# thermometer.net
KiCad netlist of a schematic drawn in EAGLE
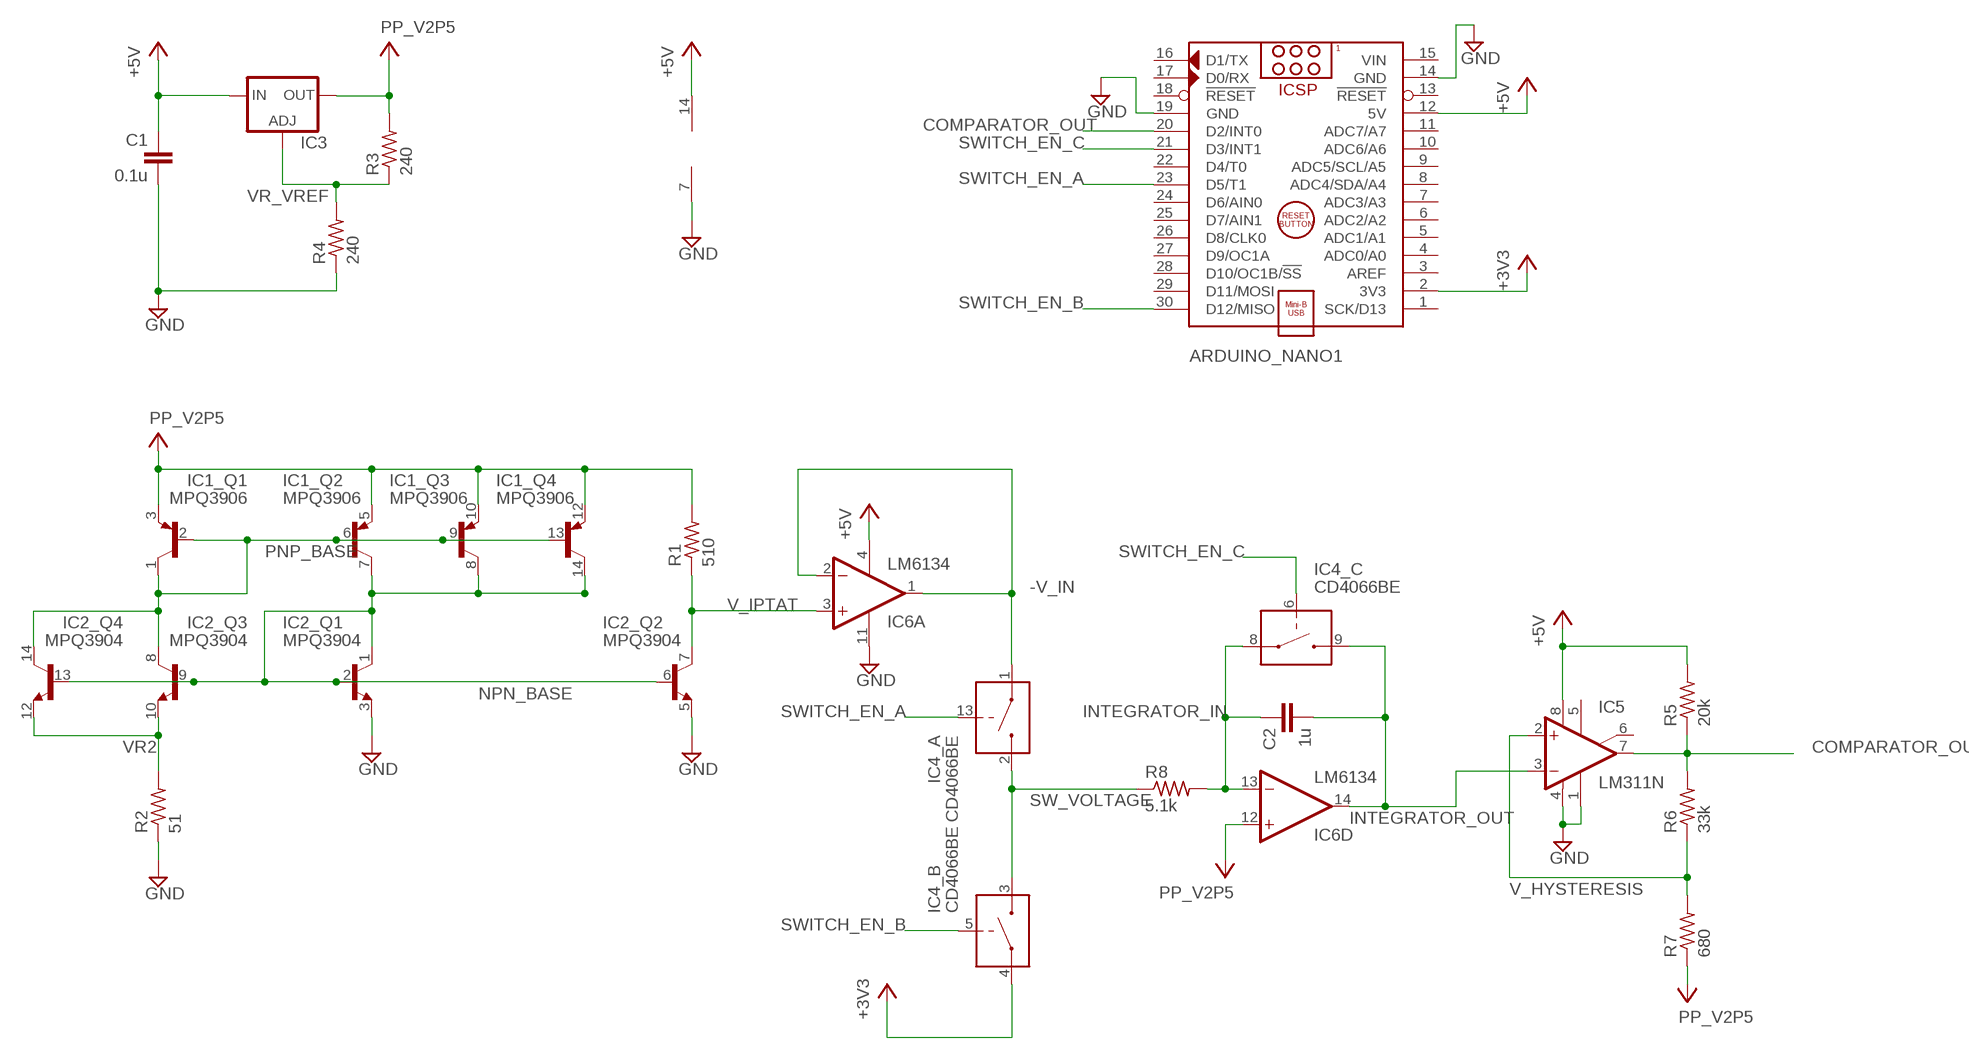
[diagram p0: schematic, sheet 1]

(export (version "E")
  (design (tool "Eeschema 10.0.6"))
  (components
    (comp (ref "ARDUINO_NANO1")
      (value "ARDUINO_NANO")
      (footprint "eagle-import:ARDUINO_NANO")
      (libsource (lib "eagle-import") (part "ARDUINO_NANO"))
    )
    (comp (ref "C1")
      (value "0.1u")
      (footprint "eagle-import:C050-035X075")
      (libsource (lib "eagle-import") (part "C-EU050-035X075"))
    )
    (comp (ref "C2")
      (value "1u")
      (footprint "eagle-import:C050-035X075")
      (libsource (lib "eagle-import") (part "C-EU050-035X075"))
    )
    (comp (ref "IC1")
      (value "MPQ3906")
      (footprint "eagle-import:DIL14")
      (libsource (lib "eagle-import") (part "MPQ3906"))
    )
    (comp (ref "IC2")
      (value "MPQ3904")
      (footprint "eagle-import:DIL14")
      (libsource (lib "eagle-import") (part "MPQ3904"))
    )
    (comp (ref "IC3")
      (value "LM317TS")
      (footprint "eagle-import:317TS")
      (libsource (lib "eagle-import") (part "LM317TS"))
    )
    (comp (ref "IC4")
      (value "CD4066BE")
      (footprint "eagle-import:DIL14")
      (libsource (lib "eagle-import") (part "CD4066BE"))
    )
    (comp (ref "IC5")
      (value "LM311N")
      (footprint "eagle-import:DIL08")
      (libsource (lib "eagle-import") (part "LM311N"))
    )
    (comp (ref "IC6")
      (value "LM6134")
      (footprint "eagle-import:DIL14")
      (libsource (lib "eagle-import") (part "LM324N"))
    )
    (comp (ref "R1")
      (value "510")
      (footprint "eagle-import:0207_10")
      (libsource (lib "eagle-import") (part "R-US_0207/10"))
    )
    (comp (ref "R2")
      (value "51")
      (footprint "eagle-import:0207_10")
      (libsource (lib "eagle-import") (part "R-US_0207/10"))
    )
    (comp (ref "R3")
      (value "240")
      (footprint "eagle-import:0207_10")
      (libsource (lib "eagle-import") (part "R-US_0207/10"))
    )
    (comp (ref "R4")
      (value "240")
      (footprint "eagle-import:0207_10")
      (libsource (lib "eagle-import") (part "R-US_0207/10"))
    )
    (comp (ref "R5")
      (value "20k")
      (footprint "eagle-import:0207_10")
      (libsource (lib "eagle-import") (part "R-US_0207/10"))
    )
    (comp (ref "R6")
      (value "33k")
      (footprint "eagle-import:0207_10")
      (libsource (lib "eagle-import") (part "R-US_0207/10"))
    )
    (comp (ref "R7")
      (value "680")
      (footprint "eagle-import:0207_10")
      (libsource (lib "eagle-import") (part "R-US_0207/10"))
    )
    (comp (ref "R8")
      (value "5.1k")
      (footprint "eagle-import:0207_10")
      (libsource (lib "eagle-import") (part "R-US_0207/10"))
    )
  )
  (nets
    (net (code "1") (name "+3V3") (class "Default")
      (node (ref "ARDUINO_NANO1") (pin "2") (pinfunction "3V3_2") (pintype "output"))
      (node (ref "IC4") (pin "4") (pinfunction "IN/OUT1_4") (pintype "bidirectional"))
    )
    (net (code "2") (name "+5V") (class "Default")
      (node (ref "ARDUINO_NANO1") (pin "12") (pinfunction "5V_12") (pintype "power_in"))
      (node (ref "C1") (pin "1") (pinfunction "1_1") (pintype "passive"))
      (node (ref "IC3") (pin "3") (pinfunction "IN_3") (pintype "input"))
      (node (ref "IC4") (pin "14") (pinfunction "V+_14") (pintype "power_in"))
      (node (ref "IC5") (pin "8") (pinfunction "V+_8") (pintype "power_in"))
      (node (ref "IC6") (pin "4") (pinfunction "V+_4") (pintype "power_in"))
      (node (ref "R5") (pin "2") (pinfunction "2_2") (pintype "passive"))
    )
    (net (code "3") (name "/-V_IN") (class "Default")
      (node (ref "IC4") (pin "1") (pinfunction "IN/OUT1_1") (pintype "bidirectional"))
      (node (ref "IC6") (pin "1") (pinfunction "OUT_1") (pintype "output"))
      (node (ref "IC6") (pin "2") (pinfunction "-IN_2") (pintype "input"))
    )
    (net (code "4") (name "/COMPARATOR_OUT") (class "Default")
      (node (ref "ARDUINO_NANO1") (pin "20") (pinfunction "D2/INT0_20") (pintype "bidirectional"))
      (node (ref "IC5") (pin "7") (pinfunction "OUT_7") (pintype "output"))
      (node (ref "R5") (pin "1") (pinfunction "1_1") (pintype "passive"))
      (node (ref "R6") (pin "2") (pinfunction "2_2") (pintype "passive"))
    )
    (net (code "5") (name "/INTEGRATOR_IN") (class "Default")
      (node (ref "C2") (pin "1") (pinfunction "1_1") (pintype "passive"))
      (node (ref "IC4") (pin "8") (pinfunction "IN/OUT1_8") (pintype "bidirectional"))
      (node (ref "IC6") (pin "13") (pinfunction "-IN_13") (pintype "input"))
      (node (ref "R8") (pin "2") (pinfunction "2_2") (pintype "passive"))
    )
    (net (code "6") (name "/INTEGRATOR_OUT") (class "Default")
      (node (ref "C2") (pin "2") (pinfunction "2_2") (pintype "passive"))
      (node (ref "IC4") (pin "9") (pinfunction "IN/OUT2_9") (pintype "bidirectional"))
      (node (ref "IC5") (pin "3") (pinfunction "-IN_3") (pintype "input"))
      (node (ref "IC6") (pin "14") (pinfunction "OUT_14") (pintype "output"))
    )
    (net (code "7") (name "/NPN_BASE") (class "Default")
      (node (ref "IC1") (pin "14") (pinfunction "C_14") (pintype "passive"))
      (node (ref "IC1") (pin "7") (pinfunction "C_7") (pintype "passive"))
      (node (ref "IC1") (pin "8") (pinfunction "C_8") (pintype "passive"))
      (node (ref "IC2") (pin "1") (pinfunction "C_1") (pintype "passive"))
      (node (ref "IC2") (pin "13") (pinfunction "B_13") (pintype "passive"))
      (node (ref "IC2") (pin "2") (pinfunction "B_2") (pintype "passive"))
      (node (ref "IC2") (pin "6") (pinfunction "B_6") (pintype "passive"))
      (node (ref "IC2") (pin "9") (pinfunction "B_9") (pintype "passive"))
    )
    (net (code "8") (name "/PNP_BASE") (class "Default")
      (node (ref "IC1") (pin "1") (pinfunction "C_1") (pintype "passive"))
      (node (ref "IC1") (pin "13") (pinfunction "B_13") (pintype "passive"))
      (node (ref "IC1") (pin "2") (pinfunction "B_2") (pintype "passive"))
      (node (ref "IC1") (pin "6") (pinfunction "B_6") (pintype "passive"))
      (node (ref "IC1") (pin "9") (pinfunction "B_9") (pintype "passive"))
      (node (ref "IC2") (pin "14") (pinfunction "C_14") (pintype "passive"))
      (node (ref "IC2") (pin "8") (pinfunction "C_8") (pintype "passive"))
    )
    (net (code "9") (name "/SWITCH_EN_A") (class "Default")
      (node (ref "ARDUINO_NANO1") (pin "23") (pinfunction "D5/T1_23") (pintype "bidirectional"))
      (node (ref "IC4") (pin "13") (pinfunction "CONTROL_13") (pintype "bidirectional"))
    )
    (net (code "10") (name "/SWITCH_EN_B") (class "Default")
      (node (ref "ARDUINO_NANO1") (pin "30") (pinfunction "D12/MISO_30") (pintype "bidirectional"))
      (node (ref "IC4") (pin "5") (pinfunction "CONTROL_5") (pintype "bidirectional"))
    )
    (net (code "11") (name "/SWITCH_EN_C") (class "Default")
      (node (ref "ARDUINO_NANO1") (pin "21") (pinfunction "D3/INT1_21") (pintype "bidirectional"))
      (node (ref "IC4") (pin "6") (pinfunction "CONTROL_6") (pintype "bidirectional"))
    )
    (net (code "12") (name "/SW_VOLTAGE") (class "Default")
      (node (ref "IC4") (pin "2") (pinfunction "IN/OUT2_2") (pintype "bidirectional"))
      (node (ref "IC4") (pin "3") (pinfunction "IN/OUT2_3") (pintype "bidirectional"))
      (node (ref "R8") (pin "1") (pinfunction "1_1") (pintype "passive"))
    )
    (net (code "13") (name "/VIN") (class "Default")
      (node (ref "ARDUINO_NANO1") (pin "15") (pinfunction "VIN_15") (pintype "power_in"))
    )
    (net (code "14") (name "/VR2") (class "Default")
      (node (ref "IC2") (pin "10") (pinfunction "E_10") (pintype "passive"))
      (node (ref "IC2") (pin "12") (pinfunction "E_12") (pintype "passive"))
      (node (ref "R2") (pin "2") (pinfunction "2_2") (pintype "passive"))
    )
    (net (code "15") (name "/VR_VREF") (class "Default")
      (node (ref "IC3") (pin "1") (pinfunction "ADJ_1") (pintype "input"))
      (node (ref "R3") (pin "1") (pinfunction "1_1") (pintype "passive"))
      (node (ref "R4") (pin "2") (pinfunction "2_2") (pintype "passive"))
    )
    (net (code "16") (name "/V_HYSTERESIS") (class "Default")
      (node (ref "IC5") (pin "2") (pinfunction "+IN_2") (pintype "input"))
      (node (ref "R6") (pin "1") (pinfunction "1_1") (pintype "passive"))
      (node (ref "R7") (pin "2") (pinfunction "2_2") (pintype "passive"))
    )
    (net (code "17") (name "/V_IPTAT") (class "Default")
      (node (ref "IC2") (pin "7") (pinfunction "C_7") (pintype "passive"))
      (node (ref "IC6") (pin "3") (pinfunction "+IN_3") (pintype "input"))
      (node (ref "R1") (pin "1") (pinfunction "1_1") (pintype "passive"))
    )
    (net (code "18") (name "GND") (class "Default")
      (node (ref "ARDUINO_NANO1") (pin "14") (pinfunction "GND_14") (pintype "power_in"))
      (node (ref "ARDUINO_NANO1") (pin "19") (pinfunction "GND_19") (pintype "power_in"))
      (node (ref "C1") (pin "2") (pinfunction "2_2") (pintype "passive"))
      (node (ref "IC2") (pin "3") (pinfunction "E_3") (pintype "passive"))
      (node (ref "IC2") (pin "5") (pinfunction "E_5") (pintype "passive"))
      (node (ref "IC4") (pin "7") (pinfunction "V-_7") (pintype "power_in"))
      (node (ref "IC5") (pin "1") (pinfunction "GND_1") (pintype "passive"))
      (node (ref "IC5") (pin "4") (pinfunction "V-_4") (pintype "power_in"))
      (node (ref "IC6") (pin "11") (pinfunction "V-_11") (pintype "power_in"))
      (node (ref "R2") (pin "1") (pinfunction "1_1") (pintype "passive"))
      (node (ref "R4") (pin "1") (pinfunction "1_1") (pintype "passive"))
    )
    (net (code "19") (name "PP_V2P5") (class "Default")
      (node (ref "IC1") (pin "10") (pinfunction "E_10") (pintype "passive"))
      (node (ref "IC1") (pin "12") (pinfunction "E_12") (pintype "passive"))
      (node (ref "IC1") (pin "3") (pinfunction "E_3") (pintype "passive"))
      (node (ref "IC1") (pin "5") (pinfunction "E_5") (pintype "passive"))
      (node (ref "IC3") (pin "2") (pinfunction "OUT_2") (pintype "passive"))
      (node (ref "IC6") (pin "12") (pinfunction "+IN_12") (pintype "input"))
      (node (ref "R1") (pin "2") (pinfunction "2_2") (pintype "passive"))
      (node (ref "R3") (pin "2") (pinfunction "2_2") (pintype "passive"))
      (node (ref "R7") (pin "1") (pinfunction "1_1") (pintype "passive"))
    )
    (net (code "20") (name "unconnected-(ARDUINO_NANO1-ADC0{slash}A0-Pad4)") (class "Default")
      (node (ref "ARDUINO_NANO1") (pin "4") (pinfunction "ADC0/A0_4") (pintype "bidirectional"))
    )
    (net (code "21") (name "unconnected-(ARDUINO_NANO1-ADC1{slash}A1-Pad5)") (class "Default")
      (node (ref "ARDUINO_NANO1") (pin "5") (pinfunction "ADC1/A1_5") (pintype "bidirectional"))
    )
    (net (code "22") (name "unconnected-(ARDUINO_NANO1-ADC2{slash}A2-Pad6)") (class "Default")
      (node (ref "ARDUINO_NANO1") (pin "6") (pinfunction "ADC2/A2_6") (pintype "bidirectional"))
    )
    (net (code "23") (name "unconnected-(ARDUINO_NANO1-ADC3{slash}A3-Pad7)") (class "Default")
      (node (ref "ARDUINO_NANO1") (pin "7") (pinfunction "ADC3/A3_7") (pintype "bidirectional"))
    )
    (net (code "24") (name "unconnected-(ARDUINO_NANO1-ADC4{slash}SDA{slash}A4-Pad8)") (class "Default")
      (node (ref "ARDUINO_NANO1") (pin "8") (pinfunction "ADC4/SDA/A4_8") (pintype "bidirectional"))
    )
    (net (code "25") (name "unconnected-(ARDUINO_NANO1-ADC5{slash}SCL{slash}A5-Pad9)") (class "Default")
      (node (ref "ARDUINO_NANO1") (pin "9") (pinfunction "ADC5/SCL/A5_9") (pintype "bidirectional"))
    )
    (net (code "26") (name "unconnected-(ARDUINO_NANO1-ADC6{slash}A6-Pad10)") (class "Default")
      (node (ref "ARDUINO_NANO1") (pin "10") (pinfunction "ADC6/A6_10") (pintype "bidirectional"))
    )
    (net (code "27") (name "unconnected-(ARDUINO_NANO1-ADC7{slash}A7-Pad11)") (class "Default")
      (node (ref "ARDUINO_NANO1") (pin "11") (pinfunction "ADC7/A7_11") (pintype "bidirectional"))
    )
    (net (code "28") (name "unconnected-(ARDUINO_NANO1-AREF-Pad3)") (class "Default")
      (node (ref "ARDUINO_NANO1") (pin "3") (pinfunction "AREF_3") (pintype "input"))
    )
    (net (code "29") (name "unconnected-(ARDUINO_NANO1-D0{slash}RX-Pad17)") (class "Default")
      (node (ref "ARDUINO_NANO1") (pin "17") (pinfunction "D0/RX_17") (pintype "bidirectional"))
    )
    (net (code "30") (name "unconnected-(ARDUINO_NANO1-D1{slash}TX-Pad16)") (class "Default")
      (node (ref "ARDUINO_NANO1") (pin "16") (pinfunction "D1/TX_16") (pintype "bidirectional"))
    )
    (net (code "31") (name "unconnected-(ARDUINO_NANO1-D4{slash}T0-Pad22)") (class "Default")
      (node (ref "ARDUINO_NANO1") (pin "22") (pinfunction "D4/T0_22") (pintype "bidirectional"))
    )
    (net (code "32") (name "unconnected-(ARDUINO_NANO1-D6{slash}AIN0-Pad24)") (class "Default")
      (node (ref "ARDUINO_NANO1") (pin "24") (pinfunction "D6/AIN0_24") (pintype "bidirectional"))
    )
    (net (code "33") (name "unconnected-(ARDUINO_NANO1-D7{slash}AIN1-Pad25)") (class "Default")
      (node (ref "ARDUINO_NANO1") (pin "25") (pinfunction "D7/AIN1_25") (pintype "bidirectional"))
    )
    (net (code "34") (name "unconnected-(ARDUINO_NANO1-D8{slash}CLK0-Pad26)") (class "Default")
      (node (ref "ARDUINO_NANO1") (pin "26") (pinfunction "D8/CLK0_26") (pintype "bidirectional"))
    )
    (net (code "35") (name "unconnected-(ARDUINO_NANO1-D9{slash}OC1A-Pad27)") (class "Default")
      (node (ref "ARDUINO_NANO1") (pin "27") (pinfunction "D9/OC1A_27") (pintype "bidirectional"))
    )
    (net (code "36") (name "unconnected-(ARDUINO_NANO1-D10{slash}OC1B{slash}~{SS}-Pad28)") (class "Default")
      (node (ref "ARDUINO_NANO1") (pin "28") (pinfunction "D10/OC1B/~{SS}_28") (pintype "bidirectional"))
    )
    (net (code "37") (name "unconnected-(ARDUINO_NANO1-D11{slash}MOSI-Pad29)") (class "Default")
      (node (ref "ARDUINO_NANO1") (pin "29") (pinfunction "D11/MOSI_29") (pintype "bidirectional"))
    )
    (net (code "38") (name "unconnected-(ARDUINO_NANO1-SCK{slash}D13-Pad1)") (class "Default")
      (node (ref "ARDUINO_NANO1") (pin "1") (pinfunction "SCK/D13_1") (pintype "bidirectional"))
    )
    (net (code "39") (name "unconnected-(ARDUINO_NANO1-~{RESET}-Pad13)") (class "Default")
      (node (ref "ARDUINO_NANO1") (pin "13") (pinfunction "~{RESET}_13") (pintype "input"))
    )
    (net (code "40") (name "unconnected-(ARDUINO_NANO1-~{RESET}-Pad18)") (class "Default")
      (node (ref "ARDUINO_NANO1") (pin "18") (pinfunction "~{RESET}_18") (pintype "input"))
    )
    (net (code "41") (name "unconnected-(IC5-ON-Pad5)") (class "Default")
      (node (ref "IC5") (pin "5") (pinfunction "ON_5") (pintype "passive"))
    )
    (net (code "42") (name "unconnected-(IC5-ON{slash}STR-Pad6)") (class "Default")
      (node (ref "IC5") (pin "6") (pinfunction "ON/STR_6") (pintype "passive"))
    )
  )
)
